# Movuino_v0_922.net
KiCad netlist of a schematic drawn in EAGLE
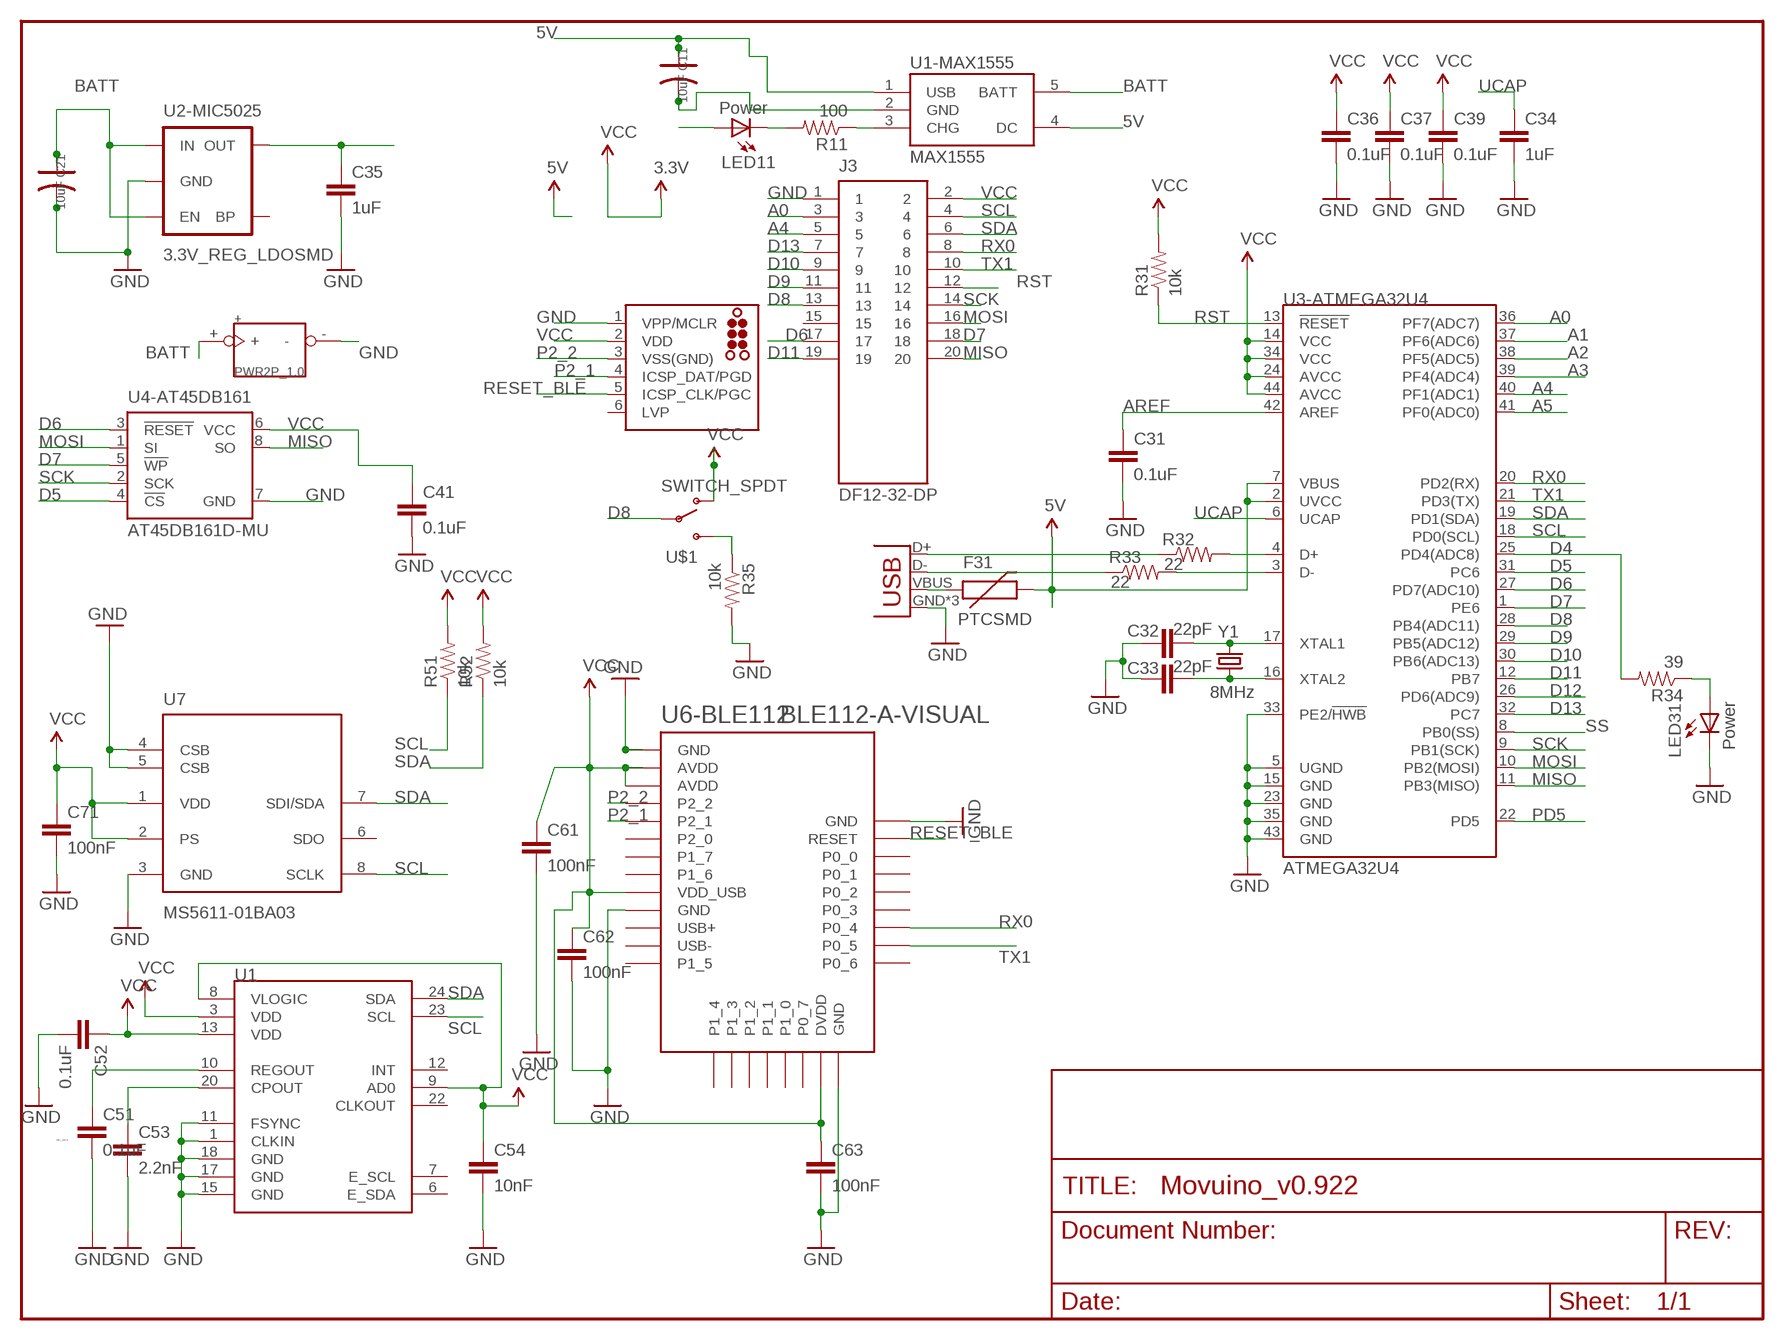
[diagram p0: schematic, sheet 1]

(export (version "E")
  (design (tool "Eeschema 10.0.6"))
  (components
    (comp (ref "+")
      (value "PWR2P_1.0")
      (footprint "eagle-import:PWR2P_1.0")
      (libsource (lib "eagle-import") (part "PWR2P_1.0"))
    )
    (comp (ref "C11")
      (value "10uF")
      (footprint "eagle-import:AVX-A")
      (libsource (lib "eagle-import") (part "C-POLAR-A"))
    )
    (comp (ref "C21")
      (value "10uF")
      (footprint "eagle-import:AVX-A")
      (libsource (lib "eagle-import") (part "C-POLAR-A"))
    )
    (comp (ref "C31")
      (value "0.1uF")
      (footprint "eagle-import:0402-CAP")
      (libsource (lib "eagle-import") (part "CAP0402-CAP"))
    )
    (comp (ref "C32")
      (value "22pF")
      (footprint "eagle-import:0402-CAP")
      (libsource (lib "eagle-import") (part "CAP0402-CAP"))
    )
    (comp (ref "C33")
      (value "22pF")
      (footprint "eagle-import:0402-CAP")
      (libsource (lib "eagle-import") (part "CAP0402-CAP"))
    )
    (comp (ref "C34")
      (value "1uF")
      (footprint "eagle-import:0402-CAP")
      (libsource (lib "eagle-import") (part "CAP0402-CAP"))
    )
    (comp (ref "C35")
      (value "1uF")
      (footprint "eagle-import:0402-CAP")
      (libsource (lib "eagle-import") (part "CAP0402-CAP"))
    )
    (comp (ref "C36")
      (value "0.1uF")
      (footprint "eagle-import:0402-CAP")
      (libsource (lib "eagle-import") (part "CAP0402-CAP"))
    )
    (comp (ref "C37")
      (value "0.1uF")
      (footprint "eagle-import:0402-CAP")
      (libsource (lib "eagle-import") (part "CAP0402-CAP"))
    )
    (comp (ref "C39")
      (value "0.1uF")
      (footprint "eagle-import:0402-CAP")
      (libsource (lib "eagle-import") (part "CAP0402-CAP"))
    )
    (comp (ref "C41")
      (value "0.1uF")
      (footprint "eagle-import:0402-CAP")
      (libsource (lib "eagle-import") (part "CAP0402-CAP"))
    )
    (comp (ref "C51")
      (value "0.1uF")
      (footprint "eagle-import:0402-CAP")
      (libsource (lib "eagle-import") (part "CAP0402-CAP"))
    )
    (comp (ref "C52")
      (value "0.1uF")
      (footprint "eagle-import:0402-CAP")
      (libsource (lib "eagle-import") (part "CAP0402-CAP"))
    )
    (comp (ref "C53")
      (value "2.2nF")
      (footprint "eagle-import:0402-CAP")
      (libsource (lib "eagle-import") (part "CAP0402-CAP"))
    )
    (comp (ref "C54")
      (value "10nF")
      (footprint "eagle-import:0402-CAP")
      (libsource (lib "eagle-import") (part "CAP0402-CAP"))
    )
    (comp (ref "C61")
      (value "100nF")
      (footprint "eagle-import:0402-CAP")
      (libsource (lib "eagle-import") (part "CAP0402-CAP"))
    )
    (comp (ref "C62")
      (value "100nF")
      (footprint "eagle-import:0402-CAP")
      (libsource (lib "eagle-import") (part "CAP0402-CAP"))
    )
    (comp (ref "C63")
      (value "100nF")
      (footprint "eagle-import:0402-CAP")
      (libsource (lib "eagle-import") (part "CAP0402-CAP"))
    )
    (comp (ref "C71")
      (value "100nF")
      (footprint "eagle-import:0402-CAP")
      (libsource (lib "eagle-import") (part "CAP0402-CAP"))
    )
    (comp (ref "F31")
      (value "PTCSMD")
      (footprint "eagle-import:PTC-1206")
      (libsource (lib "eagle-import") (part "PTCSMD"))
    )
    (comp (ref "J1")
      (value "TC2030-MCP-NL")
      (footprint "eagle-import:TC2030-MCP-NL")
      (libsource (lib "eagle-import") (part "TC2030-MCP-NL"))
    )
    (comp (ref "J3")
      (value "DF12-32-DP")
      (footprint "eagle-import:DF12-20-DP")
      (fields (field (name "PARTNO") "AS-ITM-00015"))
      (libsource (lib "eagle-import") (part "AS-ITM-00015"))
    )
    (comp (ref "LED11")
      (value "Power")
      (footprint "eagle-import:LED-0603")
      (libsource (lib "eagle-import") (part "LED0603"))
    )
    (comp (ref "LED31")
      (value "Power")
      (footprint "eagle-import:LED-0603")
      (libsource (lib "eagle-import") (part "LED0603"))
    )
    (comp (ref "R11")
      (value "100")
      (footprint "eagle-import:0402-RES")
      (libsource (lib "eagle-import") (part "RESISTOR0402-RES"))
    )
    (comp (ref "R31")
      (value "10k")
      (footprint "eagle-import:0402-RES")
      (libsource (lib "eagle-import") (part "RESISTOR0402-RES"))
    )
    (comp (ref "R32")
      (value "22")
      (footprint "eagle-import:0402-RES")
      (libsource (lib "eagle-import") (part "RESISTOR0402-RES"))
    )
    (comp (ref "R33")
      (value "22")
      (footprint "eagle-import:0402-RES")
      (libsource (lib "eagle-import") (part "RESISTOR0402-RES"))
    )
    (comp (ref "R34")
      (value "39")
      (footprint "eagle-import:0402-RES")
      (libsource (lib "eagle-import") (part "RESISTOR0402-RES"))
    )
    (comp (ref "R35")
      (value "10k")
      (footprint "eagle-import:0402-RES")
      (libsource (lib "eagle-import") (part "RESISTOR0402-RES"))
    )
    (comp (ref "R51")
      (value "10k")
      (footprint "eagle-import:0402-RES")
      (libsource (lib "eagle-import") (part "RESISTOR0402-RES"))
    )
    (comp (ref "R52")
      (value "10k")
      (footprint "eagle-import:0402-RES")
      (libsource (lib "eagle-import") (part "RESISTOR0402-RES"))
    )
    (comp (ref "U$1")
      (value "SWITCH_SPDT")
      (footprint "eagle-import:KPS-1290")
      (libsource (lib "eagle-import") (part "SWITCH_SPDT"))
    )
    (comp (ref "U1")
      (value "MPU-9150QFN-24-NP")
      (footprint "eagle-import:QFN-24-NP")
      (libsource (lib "eagle-import") (part "MPU-9150QFN-24-NP"))
    )
    (comp (ref "U1-MAX1555")
      (value "MAX1555")
      (footprint "eagle-import:SOT23-5")
      (libsource (lib "eagle-import") (part "MAX1555"))
    )
    (comp (ref "U2-MIC5025")
      (value "3.3V_REG_LDOSMD")
      (footprint "eagle-import:SOT23-5")
      (libsource (lib "eagle-import") (part "V_REG_LDOSMD"))
    )
    (comp (ref "U3-ATMEGA32U4")
      (value "ATMEGA32U4")
      (footprint "eagle-import:QFN-44-NOPAD")
      (libsource (lib "eagle-import") (part "ATMEGA32U4QFN2"))
    )
    (comp (ref "U4-AT45DB161")
      (value "AT45DB161D-MU")
      (footprint "eagle-import:VDFN-8")
      (fields (field (name "MF") "ATMEL") (field (name "MPN") "AT45DB161D-SU"))
      (libsource (lib "eagle-import") (part "AT45DB161D-MU"))
    )
    (comp (ref "U6-BLE112")
      (value "BLE112-A-VISUAL")
      (footprint "eagle-import:BLE112-A")
      (libsource (lib "eagle-import") (part "BLE112-A-VISUAL"))
    )
    (comp (ref "U7")
      (value "MS5611-01BA03")
      (footprint "eagle-import:SON125P300X500X100-8N")
      (libsource (lib "eagle-import") (part "MS5611-01BA03"))
    )
    (comp (ref "X1")
      (value "USB-MICROB")
      (footprint "eagle-import:USB-MICROB")
      (libsource (lib "eagle-import") (part "USB-MICROB"))
    )
    (comp (ref "Y1")
      (value "8MHz")
      (footprint "eagle-import:CRYSTAL-SMD-5X3")
      (libsource (lib "eagle-import") (part "CRYSTAL5X3"))
    )
  )
  (nets
    (net (code "1") (name "/A0") (class "Default")
      (node (ref "J3") (pin "3") (pinfunction "3_3") (pintype "bidirectional"))
      (node (ref "U3-ATMEGA32U4") (pin "36") (pinfunction "PF7(ADC7)_36") (pintype "bidirectional"))
    )
    (net (code "2") (name "/A1") (class "Default")
      (node (ref "U3-ATMEGA32U4") (pin "37") (pinfunction "PF6(ADC6)_37") (pintype "bidirectional"))
    )
    (net (code "3") (name "/A2") (class "Default")
      (node (ref "U3-ATMEGA32U4") (pin "38") (pinfunction "PF5(ADC5)_38") (pintype "bidirectional"))
    )
    (net (code "4") (name "/A3") (class "Default")
      (node (ref "U3-ATMEGA32U4") (pin "39") (pinfunction "PF4(ADC4)_39") (pintype "bidirectional"))
    )
    (net (code "5") (name "/A4") (class "Default")
      (node (ref "J3") (pin "5") (pinfunction "5_5") (pintype "bidirectional"))
      (node (ref "U3-ATMEGA32U4") (pin "40") (pinfunction "PF1(ADC1)_40") (pintype "bidirectional"))
    )
    (net (code "6") (name "/A5") (class "Default")
      (node (ref "U3-ATMEGA32U4") (pin "41") (pinfunction "PF0(ADC0)_41") (pintype "bidirectional"))
    )
    (net (code "7") (name "/AREF") (class "Default")
      (node (ref "C31") (pin "1") (pinfunction "1_1") (pintype "passive"))
      (node (ref "U3-ATMEGA32U4") (pin "42") (pinfunction "AREF_42") (pintype "bidirectional"))
    )
    (net (code "8") (name "/BATT") (class "Default")
      (node (ref "+") (pin "+") (pinfunction "+_+") (pintype "bidirectional"))
      (node (ref "C21") (pin "+") (pinfunction "1_+") (pintype "bidirectional"))
      (node (ref "LED11") (pin "A") (pinfunction "A_A") (pintype "passive"))
      (node (ref "U1-MAX1555") (pin "5") (pinfunction "BATT_5") (pintype "bidirectional"))
      (node (ref "U2-MIC5025") (pin "1") (pinfunction "IN_1") (pintype "input"))
      (node (ref "U2-MIC5025") (pin "3") (pinfunction "EN_3") (pintype "input"))
    )
    (net (code "9") (name "/D4") (class "Default")
      (node (ref "R34") (pin "2") (pinfunction "2_2") (pintype "passive"))
      (node (ref "U3-ATMEGA32U4") (pin "25") (pinfunction "PD4(ADC8)_25") (pintype "bidirectional"))
    )
    (net (code "10") (name "/D5") (class "Default")
      (node (ref "U3-ATMEGA32U4") (pin "31") (pinfunction "PC6_31") (pintype "bidirectional"))
      (node (ref "U4-AT45DB161") (pin "4") (pinfunction "~{CS}_4") (pintype "input"))
    )
    (net (code "11") (name "/D6") (class "Default")
      (node (ref "J3") (pin "17") (pinfunction "17_17") (pintype "bidirectional"))
      (node (ref "U3-ATMEGA32U4") (pin "27") (pinfunction "PD7(ADC10)_27") (pintype "bidirectional"))
      (node (ref "U4-AT45DB161") (pin "3") (pinfunction "~{RESET}_3") (pintype "input"))
    )
    (net (code "12") (name "/D7") (class "Default")
      (node (ref "J3") (pin "18") (pinfunction "18_18") (pintype "bidirectional"))
      (node (ref "U3-ATMEGA32U4") (pin "1") (pinfunction "PE6_1") (pintype "bidirectional"))
      (node (ref "U4-AT45DB161") (pin "5") (pinfunction "~{WP}_5") (pintype "input"))
    )
    (net (code "13") (name "/D8") (class "Default")
      (node (ref "J3") (pin "13") (pinfunction "13_13") (pintype "bidirectional"))
      (node (ref "U$1") (pin "P") (pinfunction "P_P") (pintype "passive"))
      (node (ref "U3-ATMEGA32U4") (pin "28") (pinfunction "PB4(ADC11)_28") (pintype "bidirectional"))
    )
    (net (code "14") (name "/D9") (class "Default")
      (node (ref "J3") (pin "11") (pinfunction "11_11") (pintype "bidirectional"))
      (node (ref "U3-ATMEGA32U4") (pin "29") (pinfunction "PB5(ADC12)_29") (pintype "bidirectional"))
    )
    (net (code "15") (name "/D10") (class "Default")
      (node (ref "J3") (pin "9") (pinfunction "9_9") (pintype "bidirectional"))
      (node (ref "U3-ATMEGA32U4") (pin "30") (pinfunction "PB6(ADC13)_30") (pintype "bidirectional"))
    )
    (net (code "16") (name "/D11") (class "Default")
      (node (ref "J3") (pin "19") (pinfunction "19_19") (pintype "bidirectional"))
      (node (ref "U3-ATMEGA32U4") (pin "12") (pinfunction "PB7_12") (pintype "bidirectional"))
    )
    (net (code "17") (name "/D12") (class "Default")
      (node (ref "U3-ATMEGA32U4") (pin "26") (pinfunction "PD6(ADC9)_26") (pintype "bidirectional"))
    )
    (net (code "18") (name "/D13") (class "Default")
      (node (ref "J3") (pin "7") (pinfunction "7_7") (pintype "bidirectional"))
      (node (ref "U3-ATMEGA32U4") (pin "32") (pinfunction "PC7_32") (pintype "bidirectional"))
    )
    (net (code "19") (name "/MISO") (class "Default")
      (node (ref "J3") (pin "20") (pinfunction "20_20") (pintype "bidirectional"))
      (node (ref "U3-ATMEGA32U4") (pin "11") (pinfunction "PB3(MISO)_11") (pintype "bidirectional"))
      (node (ref "U4-AT45DB161") (pin "8") (pinfunction "SO_8") (pintype "output"))
    )
    (net (code "20") (name "/MOSI") (class "Default")
      (node (ref "J3") (pin "16") (pinfunction "16_16") (pintype "bidirectional"))
      (node (ref "U3-ATMEGA32U4") (pin "10") (pinfunction "PB2(MOSI)_10") (pintype "bidirectional"))
      (node (ref "U4-AT45DB161") (pin "1") (pinfunction "SI_1") (pintype "input"))
    )
    (net (code "21") (name "/P2_1") (class "Default")
      (node (ref "J1") (pin "4") (pinfunction "ICSP_DAT/PGD_4") (pintype "bidirectional"))
      (node (ref "U6-BLE112") (pin "P2_1") (pinfunction "P2_1_P2_1") (pintype "bidirectional"))
    )
    (net (code "22") (name "/P2_2") (class "Default")
      (node (ref "J1") (pin "3") (pinfunction "VSS(GND)_3") (pintype "power_in"))
      (node (ref "U6-BLE112") (pin "P2_2") (pinfunction "P2_2_P2_2") (pintype "bidirectional"))
    )
    (net (code "23") (name "/PD5") (class "Default")
      (node (ref "U3-ATMEGA32U4") (pin "22") (pinfunction "PD5_22") (pintype "bidirectional"))
    )
    (net (code "24") (name "/RESET_BLE") (class "Default")
      (node (ref "J1") (pin "5") (pinfunction "ICSP_CLK/PGC_5") (pintype "output"))
      (node (ref "U6-BLE112") (pin "RESET") (pinfunction "RESET_RESET") (pintype "input"))
    )
    (net (code "25") (name "/RST") (class "Default")
      (node (ref "J3") (pin "12") (pinfunction "12_12") (pintype "bidirectional"))
      (node (ref "R31") (pin "1") (pinfunction "1_1") (pintype "passive"))
      (node (ref "U3-ATMEGA32U4") (pin "13") (pinfunction "~{RESET}_13") (pintype "bidirectional"))
    )
    (net (code "26") (name "/RX0") (class "Default")
      (node (ref "J3") (pin "8") (pinfunction "8_8") (pintype "bidirectional"))
      (node (ref "U3-ATMEGA32U4") (pin "20") (pinfunction "PD2(RX)_20") (pintype "bidirectional"))
      (node (ref "U6-BLE112") (pin "P0_4") (pinfunction "P0_4_P0_4") (pintype "bidirectional"))
    )
    (net (code "27") (name "/SCK") (class "Default")
      (node (ref "J3") (pin "14") (pinfunction "14_14") (pintype "bidirectional"))
      (node (ref "U3-ATMEGA32U4") (pin "9") (pinfunction "PB1(SCK)_9") (pintype "bidirectional"))
      (node (ref "U4-AT45DB161") (pin "2") (pinfunction "SCK_2") (pintype "input"))
    )
    (net (code "28") (name "/SCL") (class "Default")
      (node (ref "J3") (pin "4") (pinfunction "4_4") (pintype "bidirectional"))
      (node (ref "R51") (pin "1") (pinfunction "1_1") (pintype "passive"))
      (node (ref "U1") (pin "23") (pinfunction "SCL_23") (pintype "bidirectional"))
      (node (ref "U3-ATMEGA32U4") (pin "18") (pinfunction "PD0(SCL)_18") (pintype "bidirectional"))
      (node (ref "U7") (pin "8") (pinfunction "SCLK_8") (pintype "input"))
    )
    (net (code "29") (name "/SDA") (class "Default")
      (node (ref "J3") (pin "6") (pinfunction "6_6") (pintype "bidirectional"))
      (node (ref "R52") (pin "1") (pinfunction "1_1") (pintype "passive"))
      (node (ref "U1") (pin "24") (pinfunction "SDA_24") (pintype "bidirectional"))
      (node (ref "U3-ATMEGA32U4") (pin "19") (pinfunction "PD1(SDA)_19") (pintype "bidirectional"))
      (node (ref "U7") (pin "7") (pinfunction "SDI/SDA_7") (pintype "bidirectional"))
    )
    (net (code "30") (name "/SS") (class "Default")
      (node (ref "U3-ATMEGA32U4") (pin "8") (pinfunction "PB0(SS)_8") (pintype "bidirectional"))
    )
    (net (code "31") (name "/TX1") (class "Default")
      (node (ref "J3") (pin "10") (pinfunction "10_10") (pintype "bidirectional"))
      (node (ref "U3-ATMEGA32U4") (pin "21") (pinfunction "PD3(TX)_21") (pintype "bidirectional"))
      (node (ref "U6-BLE112") (pin "P0_5") (pinfunction "P0_5_P0_5") (pintype "bidirectional"))
    )
    (net (code "32") (name "/UCAP") (class "Default")
      (node (ref "C34") (pin "1") (pinfunction "1_1") (pintype "passive"))
      (node (ref "U3-ATMEGA32U4") (pin "6") (pinfunction "UCAP_6") (pintype "bidirectional"))
    )
    (net (code "33") (name "3.3V") (class "Default")
      (node (ref "C35") (pin "1") (pinfunction "1_1") (pintype "passive"))
      (node (ref "C36") (pin "1") (pinfunction "1_1") (pintype "passive"))
      (node (ref "C37") (pin "1") (pinfunction "1_1") (pintype "passive"))
      (node (ref "C39") (pin "1") (pinfunction "1_1") (pintype "passive"))
      (node (ref "C41") (pin "1") (pinfunction "1_1") (pintype "passive"))
      (node (ref "C52") (pin "1") (pinfunction "1_1") (pintype "passive"))
      (node (ref "C54") (pin "1") (pinfunction "1_1") (pintype "passive"))
      (node (ref "C61") (pin "1") (pinfunction "1_1") (pintype "passive"))
      (node (ref "C62") (pin "1") (pinfunction "1_1") (pintype "passive"))
      (node (ref "C63") (pin "1") (pinfunction "1_1") (pintype "passive"))
      (node (ref "C71") (pin "1") (pinfunction "1_1") (pintype "passive"))
      (node (ref "J1") (pin "2") (pinfunction "VDD_2") (pintype "power_in"))
      (node (ref "J3") (pin "2") (pinfunction "2_2") (pintype "bidirectional"))
      (node (ref "R31") (pin "2") (pinfunction "2_2") (pintype "passive"))
      (node (ref "R51") (pin "2") (pinfunction "2_2") (pintype "passive"))
      (node (ref "R52") (pin "2") (pinfunction "2_2") (pintype "passive"))
      (node (ref "U$1") (pin "O") (pinfunction "O_O") (pintype "passive"))
      (node (ref "U1") (pin "13") (pinfunction "VDD_13") (pintype "bidirectional"))
      (node (ref "U1") (pin "3") (pinfunction "VDD_3") (pintype "bidirectional"))
      (node (ref "U1") (pin "8") (pinfunction "VLOGIC_8") (pintype "bidirectional"))
      (node (ref "U1") (pin "9") (pinfunction "AD0_9") (pintype "bidirectional"))
      (node (ref "U2-MIC5025") (pin "5") (pinfunction "OUT_5") (pintype "passive"))
      (node (ref "U3-ATMEGA32U4") (pin "14") (pinfunction "VCC_14") (pintype "bidirectional"))
      (node (ref "U3-ATMEGA32U4") (pin "24") (pinfunction "AVCC_24") (pintype "bidirectional"))
      (node (ref "U3-ATMEGA32U4") (pin "34") (pinfunction "VCC_34") (pintype "bidirectional"))
      (node (ref "U3-ATMEGA32U4") (pin "44") (pinfunction "AVCC_44") (pintype "bidirectional"))
      (node (ref "U4-AT45DB161") (pin "6") (pinfunction "VCC_6") (pintype "power_in"))
      (node (ref "U6-BLE112") (pin "AVDD1") (pinfunction "AVDD_AVDD1") (pintype "power_in"))
      (node (ref "U6-BLE112") (pin "AVDD2") (pinfunction "AVDD_AVDD2") (pintype "power_in"))
      (node (ref "U6-BLE112") (pin "DVDD") (pinfunction "DVDD_DVDD") (pintype "power_in"))
      (node (ref "U6-BLE112") (pin "VDD_USB") (pinfunction "VDD_USB_VDD_USB") (pintype "power_in"))
      (node (ref "U7") (pin "1") (pinfunction "VDD_1") (pintype "power_in"))
      (node (ref "U7") (pin "2") (pinfunction "PS_2") (pintype "input"))
    )
    (net (code "34") (name "5V") (class "Default")
      (node (ref "C11") (pin "+") (pinfunction "1_+") (pintype "bidirectional"))
      (node (ref "F31") (pin "2") (pinfunction "2_2") (pintype "bidirectional"))
      (node (ref "U1-MAX1555") (pin "1") (pinfunction "USB_1") (pintype "bidirectional"))
      (node (ref "U1-MAX1555") (pin "4") (pinfunction "DC_4") (pintype "bidirectional"))
      (node (ref "U3-ATMEGA32U4") (pin "2") (pinfunction "UVCC_2") (pintype "bidirectional"))
      (node (ref "U3-ATMEGA32U4") (pin "7") (pinfunction "VBUS_7") (pintype "bidirectional"))
    )
    (net (code "35") (name "GND") (class "Default")
      (node (ref "+") (pin "-") (pinfunction "-_-") (pintype "bidirectional"))
      (node (ref "C11") (pin "-") (pinfunction "2_-") (pintype "bidirectional"))
      (node (ref "C21") (pin "-") (pinfunction "2_-") (pintype "bidirectional"))
      (node (ref "C31") (pin "2") (pinfunction "2_2") (pintype "passive"))
      (node (ref "C32") (pin "1") (pinfunction "1_1") (pintype "passive"))
      (node (ref "C33") (pin "1") (pinfunction "1_1") (pintype "passive"))
      (node (ref "C34") (pin "2") (pinfunction "2_2") (pintype "passive"))
      (node (ref "C35") (pin "2") (pinfunction "2_2") (pintype "passive"))
      (node (ref "C36") (pin "2") (pinfunction "2_2") (pintype "passive"))
      (node (ref "C37") (pin "2") (pinfunction "2_2") (pintype "passive"))
      (node (ref "C39") (pin "2") (pinfunction "2_2") (pintype "passive"))
      (node (ref "C41") (pin "2") (pinfunction "2_2") (pintype "passive"))
      (node (ref "C51") (pin "2") (pinfunction "2_2") (pintype "passive"))
      (node (ref "C52") (pin "2") (pinfunction "2_2") (pintype "passive"))
      (node (ref "C53") (pin "2") (pinfunction "2_2") (pintype "passive"))
      (node (ref "C54") (pin "2") (pinfunction "2_2") (pintype "passive"))
      (node (ref "C61") (pin "2") (pinfunction "2_2") (pintype "passive"))
      (node (ref "C62") (pin "2") (pinfunction "2_2") (pintype "passive"))
      (node (ref "C63") (pin "2") (pinfunction "2_2") (pintype "passive"))
      (node (ref "C71") (pin "2") (pinfunction "2_2") (pintype "passive"))
      (node (ref "J1") (pin "1") (pinfunction "VPP/MCLR_1") (pintype "passive"))
      (node (ref "J3") (pin "1") (pinfunction "1_1") (pintype "bidirectional"))
      (node (ref "LED31") (pin "C") (pinfunction "C_C") (pintype "passive"))
      (node (ref "R35") (pin "2") (pinfunction "2_2") (pintype "passive"))
      (node (ref "U1") (pin "1") (pinfunction "CLKIN_1") (pintype "bidirectional"))
      (node (ref "U1") (pin "11") (pinfunction "FSYNC_11") (pintype "bidirectional"))
      (node (ref "U1") (pin "15") (pinfunction "GND_15") (pintype "bidirectional"))
      (node (ref "U1") (pin "17") (pinfunction "GND_17") (pintype "bidirectional"))
      (node (ref "U1") (pin "18") (pinfunction "GND_18") (pintype "bidirectional"))
      (node (ref "U1-MAX1555") (pin "2") (pinfunction "GND_2") (pintype "bidirectional"))
      (node (ref "U2-MIC5025") (pin "2") (pinfunction "GND_2") (pintype "input"))
      (node (ref "U3-ATMEGA32U4") (pin "15") (pinfunction "GND_15") (pintype "bidirectional"))
      (node (ref "U3-ATMEGA32U4") (pin "23") (pinfunction "GND_23") (pintype "bidirectional"))
      (node (ref "U3-ATMEGA32U4") (pin "33") (pinfunction "PE2/~{HWB}_33") (pintype "bidirectional"))
      (node (ref "U3-ATMEGA32U4") (pin "35") (pinfunction "GND_35") (pintype "bidirectional"))
      (node (ref "U3-ATMEGA32U4") (pin "43") (pinfunction "GND_43") (pintype "bidirectional"))
      (node (ref "U3-ATMEGA32U4") (pin "5") (pinfunction "UGND_5") (pintype "bidirectional"))
      (node (ref "U4-AT45DB161") (pin "7") (pinfunction "GND_7") (pintype "power_in"))
      (node (ref "U6-BLE112") (pin "GND1") (pinfunction "GND_GND1") (pintype "power_in"))
      (node (ref "U6-BLE112") (pin "GND2") (pinfunction "GND_GND2") (pintype "power_in"))
      (node (ref "U6-BLE112") (pin "GND3") (pinfunction "GND_GND3") (pintype "power_in"))
      (node (ref "U6-BLE112") (pin "GND4") (pinfunction "GND_GND4") (pintype "power_in"))
      (node (ref "U7") (pin "3") (pinfunction "GND_3") (pintype "power_in"))
      (node (ref "U7") (pin "4") (pinfunction "CSB_4") (pintype "input"))
      (node (ref "U7") (pin "5") (pinfunction "CSB_5") (pintype "input"))
      (node (ref "X1") (pin "GND") (pinfunction "GND_GND") (pintype "bidirectional"))
      (node (ref "X1") (pin "MT1") (pinfunction "GND_MT1") (pintype "bidirectional"))
      (node (ref "X1") (pin "MT2") (pinfunction "GND_MT2") (pintype "bidirectional"))
    )
    (net (code "36") (name "Net-(F31-Pad1)") (class "Default")
      (node (ref "F31") (pin "1") (pinfunction "1_1") (pintype "bidirectional"))
      (node (ref "X1") (pin "VBUS") (pinfunction "VBUS_VBUS") (pintype "bidirectional"))
    )
    (net (code "37") (name "Net-(LED11-PadC)") (class "Default")
      (node (ref "LED11") (pin "C") (pinfunction "C_C") (pintype "passive"))
      (node (ref "R11") (pin "2") (pinfunction "2_2") (pintype "passive"))
    )
    (net (code "38") (name "Net-(LED31-PadA)") (class "Default")
      (node (ref "LED31") (pin "A") (pinfunction "A_A") (pintype "passive"))
      (node (ref "R34") (pin "1") (pinfunction "1_1") (pintype "passive"))
    )
    (net (code "39") (name "Net-(R32-Pad1)") (class "Default")
      (node (ref "R32") (pin "1") (pinfunction "1_1") (pintype "passive"))
      (node (ref "X1") (pin "D+") (pinfunction "D+_D+") (pintype "bidirectional"))
    )
    (net (code "40") (name "Net-(R33-Pad1)") (class "Default")
      (node (ref "R33") (pin "1") (pinfunction "1_1") (pintype "passive"))
      (node (ref "X1") (pin "D-") (pinfunction "D-_D-") (pintype "bidirectional"))
    )
    (net (code "41") (name "Net-(R35-Pad1)") (class "Default")
      (node (ref "R35") (pin "1") (pinfunction "1_1") (pintype "passive"))
      (node (ref "U$1") (pin "S") (pinfunction "S_S") (pintype "passive"))
    )
    (net (code "42") (name "Net-(U1-CPOUT)") (class "Default")
      (node (ref "C53") (pin "1") (pinfunction "1_1") (pintype "passive"))
      (node (ref "U1") (pin "20") (pinfunction "CPOUT_20") (pintype "bidirectional"))
    )
    (net (code "43") (name "Net-(U1-MAX1555-CHG)") (class "Default")
      (node (ref "R11") (pin "1") (pinfunction "1_1") (pintype "passive"))
      (node (ref "U1-MAX1555") (pin "3") (pinfunction "CHG_3") (pintype "bidirectional"))
    )
    (net (code "44") (name "Net-(U1-REGOUT)") (class "Default")
      (node (ref "C51") (pin "1") (pinfunction "1_1") (pintype "passive"))
      (node (ref "U1") (pin "10") (pinfunction "REGOUT_10") (pintype "bidirectional"))
    )
    (net (code "45") (name "Net-(U3-ATMEGA32U4-D+)") (class "Default")
      (node (ref "R32") (pin "2") (pinfunction "2_2") (pintype "passive"))
      (node (ref "U3-ATMEGA32U4") (pin "4") (pinfunction "D+_4") (pintype "bidirectional"))
    )
    (net (code "46") (name "Net-(U3-ATMEGA32U4-D-)") (class "Default")
      (node (ref "R33") (pin "2") (pinfunction "2_2") (pintype "passive"))
      (node (ref "U3-ATMEGA32U4") (pin "3") (pinfunction "D-_3") (pintype "bidirectional"))
    )
    (net (code "47") (name "Net-(U3-ATMEGA32U4-XTAL1)") (class "Default")
      (node (ref "C32") (pin "2") (pinfunction "2_2") (pintype "passive"))
      (node (ref "U3-ATMEGA32U4") (pin "17") (pinfunction "XTAL1_17") (pintype "bidirectional"))
      (node (ref "Y1") (pin "3") (pinfunction "2_3") (pintype "passive"))
    )
    (net (code "48") (name "Net-(U3-ATMEGA32U4-XTAL2)") (class "Default")
      (node (ref "C33") (pin "2") (pinfunction "2_2") (pintype "passive"))
      (node (ref "U3-ATMEGA32U4") (pin "16") (pinfunction "XTAL2_16") (pintype "bidirectional"))
      (node (ref "Y1") (pin "1") (pinfunction "1_1") (pintype "passive"))
    )
    (net (code "49") (name "unconnected-(J1-LVP-Pad6)") (class "Default")
      (node (ref "J1") (pin "6") (pinfunction "LVP_6") (pintype "bidirectional"))
    )
    (net (code "50") (name "unconnected-(J3-Pad15)") (class "Default")
      (node (ref "J3") (pin "15") (pinfunction "15_15") (pintype "bidirectional"))
    )
    (net (code "51") (name "unconnected-(U1-CLKOUT-Pad22)") (class "Default")
      (node (ref "U1") (pin "22") (pinfunction "CLKOUT_22") (pintype "bidirectional"))
    )
    (net (code "52") (name "unconnected-(U1-E_SCL-Pad7)") (class "Default")
      (node (ref "U1") (pin "7") (pinfunction "E_SCL_7") (pintype "bidirectional"))
    )
    (net (code "53") (name "unconnected-(U1-E_SDA-Pad6)") (class "Default")
      (node (ref "U1") (pin "6") (pinfunction "E_SDA_6") (pintype "bidirectional"))
    )
    (net (code "54") (name "unconnected-(U1-INT-Pad12)") (class "Default")
      (node (ref "U1") (pin "12") (pinfunction "INT_12") (pintype "bidirectional"))
    )
    (net (code "55") (name "unconnected-(U2-MIC5025-BP-Pad4)") (class "Default")
      (node (ref "U2-MIC5025") (pin "4") (pinfunction "BP_4") (pintype "input"))
    )
    (net (code "56") (name "unconnected-(U6-BLE112-PadP0_0)") (class "Default")
      (node (ref "U6-BLE112") (pin "P0_0") (pinfunction "P0_0_P0_0") (pintype "bidirectional"))
    )
    (net (code "57") (name "unconnected-(U6-BLE112-PadP0_1)") (class "Default")
      (node (ref "U6-BLE112") (pin "P0_1") (pinfunction "P0_1_P0_1") (pintype "bidirectional"))
    )
    (net (code "58") (name "unconnected-(U6-BLE112-PadP0_2)") (class "Default")
      (node (ref "U6-BLE112") (pin "P0_2") (pinfunction "P0_2_P0_2") (pintype "bidirectional"))
    )
    (net (code "59") (name "unconnected-(U6-BLE112-PadP0_3)") (class "Default")
      (node (ref "U6-BLE112") (pin "P0_3") (pinfunction "P0_3_P0_3") (pintype "bidirectional"))
    )
    (net (code "60") (name "unconnected-(U6-BLE112-PadP0_6)") (class "Default")
      (node (ref "U6-BLE112") (pin "P0_6") (pinfunction "P0_6_P0_6") (pintype "bidirectional"))
    )
    (net (code "61") (name "unconnected-(U6-BLE112-PadP0_7)") (class "Default")
      (node (ref "U6-BLE112") (pin "P0_7") (pinfunction "P0_7_P0_7") (pintype "bidirectional"))
    )
    (net (code "62") (name "unconnected-(U6-BLE112-PadP1_0)") (class "Default")
      (node (ref "U6-BLE112") (pin "P1_0") (pinfunction "P1_0_P1_0") (pintype "bidirectional"))
    )
    (net (code "63") (name "unconnected-(U6-BLE112-PadP1_1)") (class "Default")
      (node (ref "U6-BLE112") (pin "P1_1") (pinfunction "P1_1_P1_1") (pintype "bidirectional"))
    )
    (net (code "64") (name "unconnected-(U6-BLE112-PadP1_2)") (class "Default")
      (node (ref "U6-BLE112") (pin "P1_2") (pinfunction "P1_2_P1_2") (pintype "bidirectional"))
    )
    (net (code "65") (name "unconnected-(U6-BLE112-PadP1_3)") (class "Default")
      (node (ref "U6-BLE112") (pin "P1_3") (pinfunction "P1_3_P1_3") (pintype "bidirectional"))
    )
    (net (code "66") (name "unconnected-(U6-BLE112-PadP1_4)") (class "Default")
      (node (ref "U6-BLE112") (pin "P1_4") (pinfunction "P1_4_P1_4") (pintype "bidirectional"))
    )
    (net (code "67") (name "unconnected-(U6-BLE112-PadP1_5)") (class "Default")
      (node (ref "U6-BLE112") (pin "P1_5") (pinfunction "P1_5_P1_5") (pintype "bidirectional"))
    )
    (net (code "68") (name "unconnected-(U6-BLE112-PadP1_6)") (class "Default")
      (node (ref "U6-BLE112") (pin "P1_6") (pinfunction "P1_6_P1_6") (pintype "bidirectional"))
    )
    (net (code "69") (name "unconnected-(U6-BLE112-PadP1_7)") (class "Default")
      (node (ref "U6-BLE112") (pin "P1_7") (pinfunction "P1_7_P1_7") (pintype "bidirectional"))
    )
    (net (code "70") (name "unconnected-(U6-BLE112-PadP2_0)") (class "Default")
      (node (ref "U6-BLE112") (pin "P2_0") (pinfunction "P2_0_P2_0") (pintype "bidirectional"))
    )
    (net (code "71") (name "unconnected-(U6-BLE112-PadUSB+)") (class "Default")
      (node (ref "U6-BLE112") (pin "USB+") (pinfunction "USB+_USB+") (pintype "bidirectional"))
    )
    (net (code "72") (name "unconnected-(U6-BLE112-PadUSB-)") (class "Default")
      (node (ref "U6-BLE112") (pin "USB-") (pinfunction "USB-_USB-") (pintype "bidirectional"))
    )
    (net (code "73") (name "unconnected-(U7-SDO-Pad6)") (class "Default")
      (node (ref "U7") (pin "6") (pinfunction "SDO_6") (pintype "output"))
    )
  )
)
